# Power_Supply.net
KiCad netlist of a schematic drawn in Altium Designer
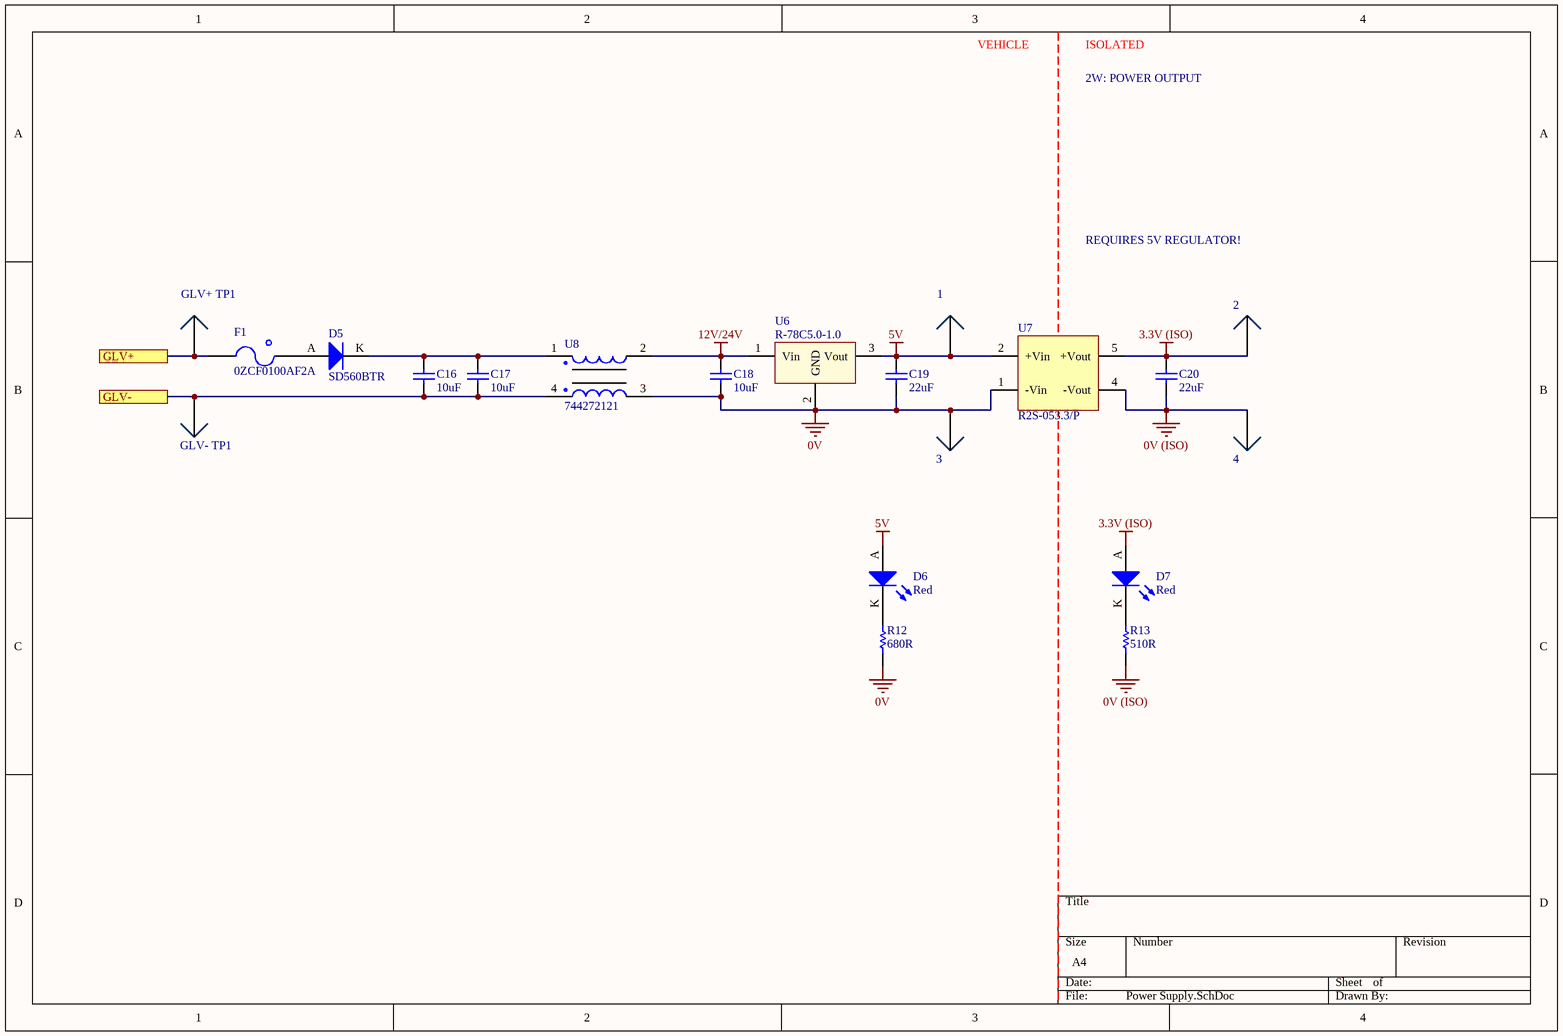
[diagram p0: Power Supply.SchDoc]

(export (version "E")
  (design (tool "Eeschema 10.0.6"))
  (components
    (comp (ref "1")
      (value "0mm")
      (footprint "SMD Test Point")
      (fields (field (name "PART NUMBER") "SMD Test Point") (field (name "CONTACT") "NA"))
      (libsource (lib "ts_20-standard-connectors") (part "Test Point"))
    )
    (comp (ref "2")
      (value "0mm")
      (footprint "SMD Test Point")
      (fields (field (name "PART NUMBER") "SMD Test Point") (field (name "CONTACT") "NA"))
      (libsource (lib "ts_20-standard-connectors") (part "Test Point"))
    )
    (comp (ref "3")
      (value "0mm")
      (footprint "SMD Test Point")
      (fields (field (name "PART NUMBER") "SMD Test Point") (field (name "CONTACT") "NA"))
      (libsource (lib "ts_20-standard-connectors") (part "Test Point"))
    )
    (comp (ref "4")
      (value "0mm")
      (footprint "SMD Test Point")
      (fields (field (name "PART NUMBER") "SMD Test Point") (field (name "CONTACT") "NA"))
      (libsource (lib "ts_20-standard-connectors") (part "Test Point"))
    )
    (comp (ref "C16")
      (value "10uF")
      (footprint "0805")
      (fields
        (field (name "PART NUMBER") "GRM21BR6YA106KE43L")
        (field (name "TOLERANCE") "10%")
        (field (name "MANUFACTURER") "muRata")
      )
      (libsource (lib "ts_20-standard-library") (part "Capacitor"))
    )
    (comp (ref "C17")
      (value "10uF")
      (footprint "0805")
      (fields
        (field (name "PART NUMBER") "GRM21BR6YA106KE43L")
        (field (name "TOLERANCE") "10%")
        (field (name "MANUFACTURER") "muRata")
      )
      (libsource (lib "ts_20-standard-library") (part "Capacitor"))
    )
    (comp (ref "C18")
      (value "10uF")
      (footprint "0805")
      (fields
        (field (name "PART NUMBER") "GRM21BR6YA106KE43L")
        (field (name "TOLERANCE") "10%")
        (field (name "MANUFACTURER") "muRata")
      )
      (libsource (lib "ts_20-standard-library") (part "Capacitor"))
    )
    (comp (ref "C19")
      (value "22uF")
      (footprint "1206")
      (fields
        (field (name "PART NUMBER") "CC1206MKX5R7BB226")
        (field (name "TOLERANCE") "20%")
        (field (name "MANUFACTURER") "YAGEO")
      )
      (libsource (lib "ts_20-standard-library") (part "Capacitor"))
    )
    (comp (ref "C20")
      (value "22uF")
      (footprint "1206")
      (fields
        (field (name "PART NUMBER") "CC1206MKX5R7BB226")
        (field (name "TOLERANCE") "20%")
        (field (name "MANUFACTURER") "YAGEO")
      )
      (libsource (lib "ts_20-standard-library") (part "Capacitor"))
    )
    (comp (ref "D5")
      (value "SD560BTR")
      (footprint "SMB Diode")
      (description "1.2V_F 600V 5A SMB")
      (fields
        (field (name "MANUFACTURER") "SMC Diode Solutions")
        (field (name "DIGIKEY PART NUMBER") "1655-1530-2-ND")
      )
      (libsource (lib "ts_20-standard-library") (part "Diode"))
    )
    (comp (ref "D6")
      (value "Red")
      (footprint "0805 LED")
      (description "Red LED Indication - Discrete 1.75V 0805 (2012 Metric)")
      (fields (field (name "PART NUMBER") "SML-210LTT86") (field (name "MANUFACTURER") "ROHM Semiconductor"))
      (libsource (lib "ts_20-standard-library") (part "LED"))
    )
    (comp (ref "D7")
      (value "Red")
      (footprint "0805 LED")
      (description "Red LED Indication - Discrete 1.75V 0805 (2012 Metric)")
      (fields (field (name "PART NUMBER") "SML-210LTT86") (field (name "MANUFACTURER") "ROHM Semiconductor"))
      (libsource (lib "ts_20-standard-library") (part "LED"))
    )
    (comp (ref "F1")
      (value "0ZCF0100AF2A")
      (footprint "2920")
      (description "PTC RESET FUSE 60V 1A 292")
      (fields
        (field (name "MANUFACTURER") "Littelfuse Inc.")
        (field (name "DIGIKEY PART NUMBER") "507-2070-1-ND")
      )
      (libsource (lib "ts_20-standard-library") (part "PTC Fuse"))
    )
    (comp (ref "GLV+ TP1")
      (value "0mm")
      (footprint "SMD Test Point")
      (fields (field (name "PART NUMBER") "SMD Test Point") (field (name "CONTACT") "NA"))
      (libsource (lib "ts_20-standard-connectors") (part "Test Point"))
    )
    (comp (ref "GLV- TP1")
      (value "0mm")
      (footprint "SMD Test Point")
      (fields (field (name "PART NUMBER") "SMD Test Point") (field (name "CONTACT") "NA"))
      (libsource (lib "ts_20-standard-connectors") (part "Test Point"))
    )
    (comp (ref "R12")
      (value "680R")
      (footprint "0805")
      (fields
        (field (name "PART NUMBER") "RC0805FR07680RL")
        (field (name "MANUFACTURER") "YAGEO")
        (field (name "TOLERANCE") "0.01")
      )
      (libsource (lib "ts_20-standard-library") (part "Resistor"))
    )
    (comp (ref "R13")
      (value "510R")
      (footprint "0805")
      (fields
        (field (name "PART NUMBER") "RC0805FR07510RL")
        (field (name "MANUFACTURER") "YAGEO")
        (field (name "TOLERANCE") "0.01")
      )
      (libsource (lib "ts_20-standard-library") (part "Resistor"))
    )
    (comp (ref "U6")
      (value "R-78C5.0-1.0")
      (footprint "RECOM 3-SIP")
      (description "CONV DC/DC 1A 5V OUT SIP VERT")
      (fields (field (name "MANUFACTURER") "Recom") (field (name "DIGIKEY PART NUMBER") "945-1395-5-ND"))
      (libsource (lib "ts_20-standard-library") (part "R-78C5.0-1.0"))
    )
    (comp (ref "U7")
      (value "R2S-053.3/P")
      (footprint "RECOM 8-SMD (5 Pin)")
      (description "Isolated Module DC DC Converter 1 Output 3.3V 606mA 4.5V - 5.5V Input")
      (fields (field (name "MANUFACTURER") "Recom") (field (name "DIGIKEY PART NUMBER") "945-2677-5-ND"))
      (libsource (lib "ts_20-standard-library") (part "R2S-053.3/P"))
    )
    (comp (ref "U8")
      (value "744272121")
      (footprint "Wurth 4-PC Pad")
      (description "120µH @ 100kHz 2 Line Common Mode Choke Surface Mount 460 Ohms @ 30MHz 2.5A DCR 25mOhm")
      (fields
        (field (name "MANUFACTURER") "Wurth Electronics Inc")
        (field (name "DIGIKEY PART NUMBER") "732-1489-1-ND")
      )
      (libsource (lib "ts_20-standard-library") (part "744272121"))
    )
  )
  (nets
    (net (code "1") (name "/GLV+") (class "Default")
      (node (ref "F1") (pin "1") (pinfunction "1_1") (pintype "passive"))
      (node (ref "GLV+ TP1") (pin "1") (pinfunction "1_1") (pintype "passive"))
    )
    (net (code "2") (name "/GLV-") (class "Default")
      (node (ref "C16") (pin "1") (pinfunction "1_1") (pintype "passive"))
      (node (ref "C17") (pin "1") (pinfunction "1_1") (pintype "passive"))
      (node (ref "GLV- TP1") (pin "1") (pinfunction "1_1") (pintype "passive"))
      (node (ref "U8") (pin "4") (pinfunction "4_4") (pintype "passive"))
    )
    (net (code "3") (name "0V") (class "Default")
      (node (ref "3") (pin "1") (pinfunction "1_1") (pintype "passive"))
      (node (ref "C18") (pin "1") (pinfunction "1_1") (pintype "passive"))
      (node (ref "C19") (pin "1") (pinfunction "1_1") (pintype "passive"))
      (node (ref "R12") (pin "1") (pinfunction "1_1") (pintype "passive"))
      (node (ref "U6") (pin "2") (pinfunction "GND_2") (pintype "passive"))
      (node (ref "U7") (pin "1") (pinfunction "-Vin_1") (pintype "power_in"))
      (node (ref "U8") (pin "3") (pinfunction "3_3") (pintype "power_in"))
    )
    (net (code "4") (name "0V (ISO)") (class "Default")
      (node (ref "4") (pin "1") (pinfunction "1_1") (pintype "passive"))
      (node (ref "C20") (pin "1") (pinfunction "1_1") (pintype "passive"))
      (node (ref "R13") (pin "1") (pinfunction "1_1") (pintype "passive"))
      (node (ref "U7") (pin "4") (pinfunction "-Vout_4") (pintype "power_in"))
    )
    (net (code "5") (name "3.3V (ISO)") (class "Default")
      (node (ref "2") (pin "1") (pinfunction "1_1") (pintype "passive"))
      (node (ref "C20") (pin "2") (pinfunction "2_2") (pintype "passive"))
      (node (ref "D7") (pin "A") (pinfunction "A_A") (pintype "passive"))
      (node (ref "U7") (pin "5") (pinfunction "+Vout_5") (pintype "power_in"))
    )
    (net (code "6") (name "5V") (class "Default")
      (node (ref "1") (pin "1") (pinfunction "1_1") (pintype "passive"))
      (node (ref "C19") (pin "2") (pinfunction "2_2") (pintype "passive"))
      (node (ref "D6") (pin "A") (pinfunction "A_A") (pintype "passive"))
      (node (ref "U6") (pin "3") (pinfunction "Vout_3") (pintype "passive"))
      (node (ref "U7") (pin "2") (pinfunction "+Vin_2") (pintype "power_in"))
    )
    (net (code "7") (name "12V{slash}24V") (class "Default")
      (node (ref "C18") (pin "2") (pinfunction "2_2") (pintype "passive"))
      (node (ref "U6") (pin "1") (pinfunction "Vin_1") (pintype "passive"))
      (node (ref "U8") (pin "2") (pinfunction "2_2") (pintype "passive"))
    )
    (net (code "8") (name "Net-(C16-Pad2)") (class "Default")
      (node (ref "C16") (pin "2") (pinfunction "2_2") (pintype "passive"))
      (node (ref "C17") (pin "2") (pinfunction "2_2") (pintype "passive"))
      (node (ref "D5") (pin "K") (pinfunction "K_K") (pintype "passive"))
      (node (ref "U8") (pin "1") (pinfunction "1_1") (pintype "passive"))
    )
    (net (code "9") (name "Net-(D5-PadA)") (class "Default")
      (node (ref "D5") (pin "A") (pinfunction "A_A") (pintype "passive"))
      (node (ref "F1") (pin "2") (pinfunction "2_2") (pintype "passive"))
    )
    (net (code "10") (name "Net-(D6-PadK)") (class "Default")
      (node (ref "D6") (pin "K") (pinfunction "K_K") (pintype "passive"))
      (node (ref "R12") (pin "2") (pinfunction "2_2") (pintype "passive"))
    )
    (net (code "11") (name "Net-(D7-PadK)") (class "Default")
      (node (ref "D7") (pin "K") (pinfunction "K_K") (pintype "passive"))
      (node (ref "R13") (pin "2") (pinfunction "2_2") (pintype "passive"))
    )
  )
)
